# 9-Axis.net
KiCad netlist of a schematic drawn in Altium Designer
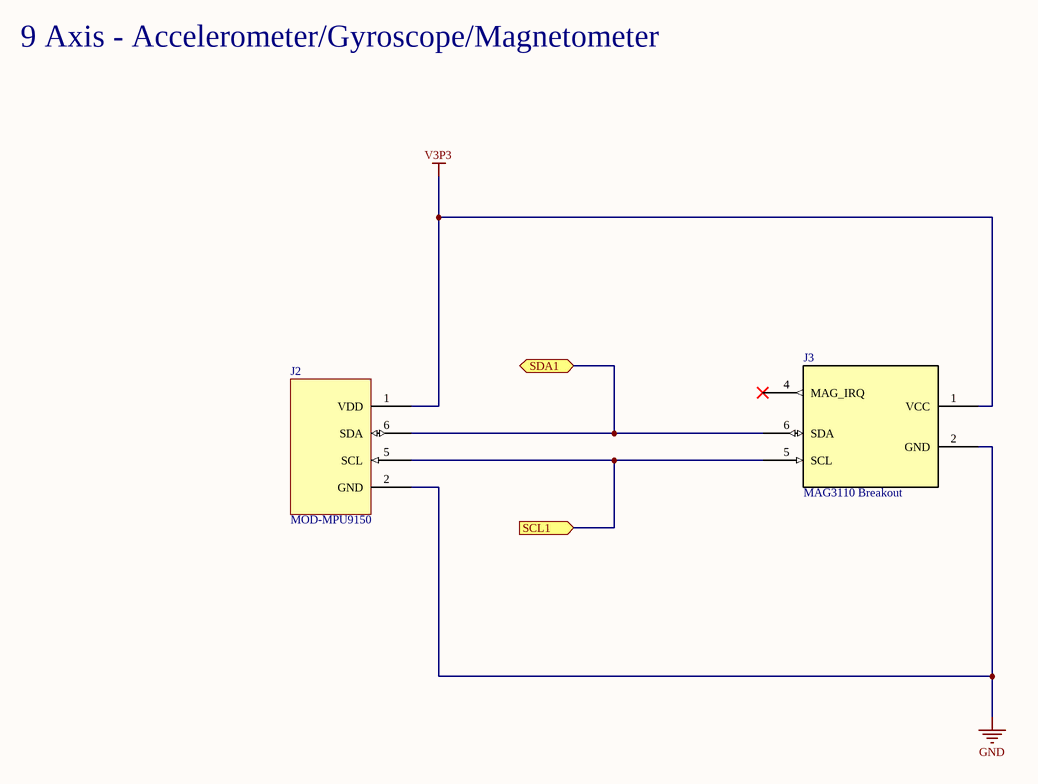
[diagram p0: 9-Axis.SchDoc]

(export (version "E")
  (design (tool "Eeschema 10.0.6"))
  (components
    (comp (ref "J2")
      (value "MOD-MPU9150")
      (footprint "PcbLib1:UEXT_MALE x10")
      (description "9-Axis")
      (libsource (lib "Schlib") (part "MOD-MPU9150"))
    )
    (comp (ref "J3")
      (value "MAG3110 Breakout")
      (footprint "UEXT_MALE x10")
      (libsource (lib "Schlib") (part "MOD-MAG3110"))
    )
  )
  (nets
    (net (code "1") (name "/SCL1") (class "Default")
      (node (ref "J2") (pin "5") (pinfunction "SCL_5") (pintype "input"))
      (node (ref "J3") (pin "5") (pinfunction "SCL_5") (pintype "input"))
    )
    (net (code "2") (name "/SDA1") (class "Default")
      (node (ref "J2") (pin "6") (pinfunction "SDA_6") (pintype "bidirectional"))
      (node (ref "J3") (pin "6") (pinfunction "SDA_6") (pintype "bidirectional"))
    )
    (net (code "3") (name "GND") (class "Default")
      (node (ref "J2") (pin "2") (pinfunction "GND_2") (pintype "power_in"))
      (node (ref "J3") (pin "2") (pinfunction "GND_2") (pintype "power_in"))
    )
    (net (code "4") (name "V3P3") (class "Default")
      (node (ref "J2") (pin "1") (pinfunction "VDD_1") (pintype "power_in"))
      (node (ref "J3") (pin "1") (pinfunction "VCC_1") (pintype "power_in"))
    )
    (net (code "5") (name "unconnected-(J3-MAG_IRQ-Pad4)") (class "Default")
      (node (ref "J3") (pin "4") (pinfunction "MAG_IRQ_4") (pintype "output+no_connect"))
    )
  )
)
